# SH08_-_OMAP-L137_EMIF_A.net
KiCad netlist of a schematic drawn in Altium Designer
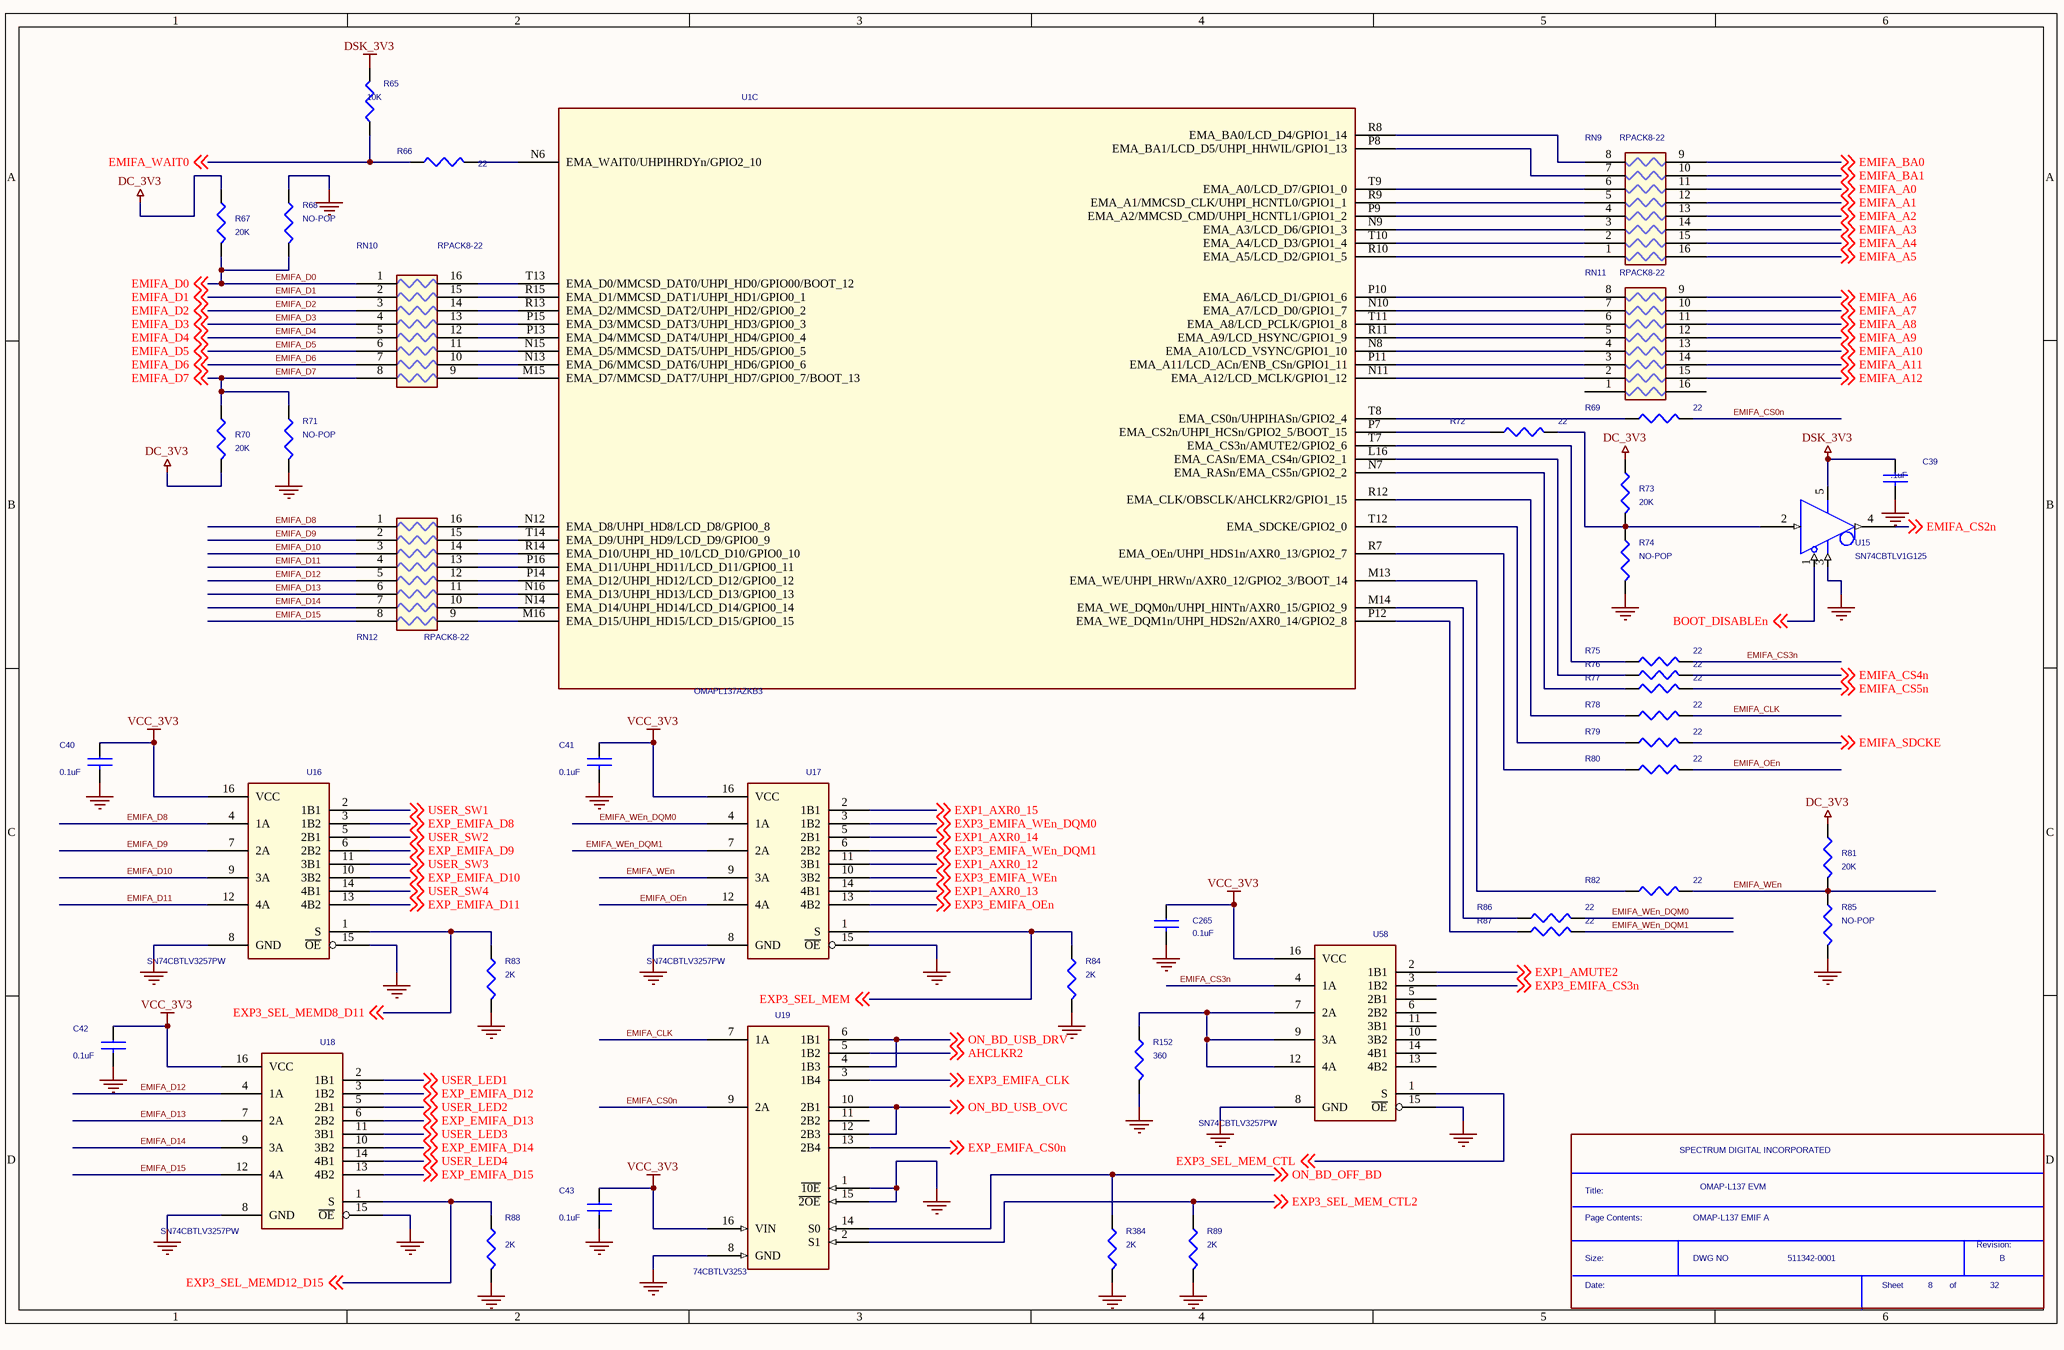
[diagram p0: SH08 - OMAP-L137 EMIF A.SchDoc]

(export (version "E")
  (design (tool "Eeschema 10.0.6"))
  (components
    (comp (ref "C39")
      (value ".1uF")
      (footprint "c402-25")
      (fields (field (name "PART #") "101587-1100R"))
      (libsource (lib "*") (part "CAP NP_2"))
    )
    (comp (ref "C40")
      (value "0.1uF")
      (footprint "c402-25")
      (fields (field (name "PART #") "101587-1100R"))
      (libsource (lib "*") (part "CAP NP"))
    )
    (comp (ref "C41")
      (value "0.1uF")
      (footprint "c402-25")
      (fields (field (name "PART #") "101587-1100R"))
      (libsource (lib "*") (part "CAP NP"))
    )
    (comp (ref "C42")
      (value "0.1uF")
      (footprint "c402-25")
      (fields (field (name "PART #") "101587-1100R"))
      (libsource (lib "*") (part "CAP NP"))
    )
    (comp (ref "C43")
      (value "0.1uF")
      (footprint "c402-25")
      (fields (field (name "PART #") "101587-1100R"))
      (libsource (lib "*") (part "CAP NP"))
    )
    (comp (ref "C265")
      (value "0.1uF")
      (footprint "c402-25")
      (fields (field (name "PART #") "101587-1100R"))
      (libsource (lib "*") (part "CAP NP_2"))
    )
    (comp (ref "R65")
      (value "10K")
      (footprint "r402-25")
      (fields (field (name "PART #") "101370-1003R"))
      (libsource (lib "*") (part "R"))
    )
    (comp (ref "R66")
      (value "22")
      (footprint "r402-25")
      (fields (field (name "PART #") "101370-2200R"))
      (libsource (lib "*") (part "R"))
    )
    (comp (ref "R67")
      (value "20K")
      (footprint "r402-25")
      (fields (field (name "PART #") "101370-2003R"))
      (libsource (lib "*") (part "R_1"))
    )
    (comp (ref "R68")
      (value "NO-POP")
      (footprint "r402-25")
      (fields (field (name "PART #") "R0402-NOPOP"))
      (libsource (lib "*") (part "R_1"))
    )
    (comp (ref "R69")
      (value "22")
      (footprint "r402-25")
      (fields (field (name "PART #") "101370-2200R"))
      (libsource (lib "*") (part "R"))
    )
    (comp (ref "R70")
      (value "20K")
      (footprint "r402-25")
      (fields (field (name "PART #") "101370-2003R"))
      (libsource (lib "*") (part "R_1"))
    )
    (comp (ref "R71")
      (value "NO-POP")
      (footprint "r402-25")
      (fields (field (name "PART #") "R0402-NOPOP"))
      (libsource (lib "*") (part "R_1"))
    )
    (comp (ref "R72")
      (value "22")
      (footprint "r402-25")
      (fields (field (name "PART #") "101370-2200R"))
      (libsource (lib "*") (part "R"))
    )
    (comp (ref "R73")
      (value "20K")
      (footprint "r402-25")
      (fields (field (name "PART #") "101370-2003R"))
      (libsource (lib "*") (part "R_1"))
    )
    (comp (ref "R74")
      (value "NO-POP")
      (footprint "r402-25")
      (fields (field (name "PART #") "R0402-NOPOP"))
      (libsource (lib "*") (part "R_1"))
    )
    (comp (ref "R75")
      (value "22")
      (footprint "r402-25")
      (fields (field (name "PART #") "101370-2200R"))
      (libsource (lib "*") (part "R"))
    )
    (comp (ref "R76")
      (value "22")
      (footprint "r402-25")
      (fields (field (name "PART #") "101370-2200R"))
      (libsource (lib "*") (part "R"))
    )
    (comp (ref "R77")
      (value "22")
      (footprint "r402-25")
      (fields (field (name "PART #") "101370-2200R"))
      (libsource (lib "*") (part "R"))
    )
    (comp (ref "R78")
      (value "22")
      (footprint "r402-25")
      (fields (field (name "PART #") "101370-2200R"))
      (libsource (lib "*") (part "R"))
    )
    (comp (ref "R79")
      (value "22")
      (footprint "r402-25")
      (fields (field (name "PART #") "101370-2200R"))
      (libsource (lib "*") (part "R"))
    )
    (comp (ref "R80")
      (value "22")
      (footprint "r402-25")
      (fields (field (name "PART #") "101370-2200R"))
      (libsource (lib "*") (part "R"))
    )
    (comp (ref "R81")
      (value "20K")
      (footprint "r402-25")
      (fields (field (name "PART #") "101370-2003R"))
      (libsource (lib "*") (part "R_1"))
    )
    (comp (ref "R82")
      (value "22")
      (footprint "r402-25")
      (fields (field (name "PART #") "101370-2200R"))
      (libsource (lib "*") (part "R"))
    )
    (comp (ref "R83")
      (value "2K")
      (footprint "r402-25")
      (fields (field (name "PART #") "101370-2002R"))
      (libsource (lib "*") (part "R"))
    )
    (comp (ref "R84")
      (value "2K")
      (footprint "r402-25")
      (fields (field (name "PART #") "101370-2002R"))
      (libsource (lib "*") (part "R"))
    )
    (comp (ref "R85")
      (value "NO-POP")
      (footprint "r402-25")
      (fields (field (name "PART #") "R0402-NOPOP"))
      (libsource (lib "*") (part "R_1"))
    )
    (comp (ref "R86")
      (value "22")
      (footprint "r402-25")
      (fields (field (name "PART #") "101370-2200R"))
      (libsource (lib "*") (part "R"))
    )
    (comp (ref "R87")
      (value "22")
      (footprint "r402-25")
      (fields (field (name "PART #") "101370-2200R"))
      (libsource (lib "*") (part "R"))
    )
    (comp (ref "R88")
      (value "2K")
      (footprint "r402-25")
      (fields (field (name "PART #") "101370-2002R"))
      (libsource (lib "*") (part "R"))
    )
    (comp (ref "R89")
      (value "2K")
      (footprint "r402-25")
      (fields (field (name "PART #") "101370-2002R"))
      (libsource (lib "*") (part "R"))
    )
    (comp (ref "R152")
      (value "360")
      (footprint "r402-25")
      (fields (field (name "PART #") "101370-3601R"))
      (libsource (lib "*") (part "R"))
    )
    (comp (ref "R384")
      (value "2K")
      (footprint "r402-25")
      (fields (field (name "PART #") "101370-2002R"))
      (libsource (lib "*") (part "R"))
    )
    (comp (ref "RN9")
      (value "RPACK8-22")
      (footprint "rpak16-10x25-2hv")
      (fields (field (name "PART #") "101069-2200R"))
      (libsource (lib "*") (part "RESISTOR DIP 8_0"))
    )
    (comp (ref "RN10")
      (value "RPACK8-22")
      (footprint "rpak16-10x25-2hv")
      (fields (field (name "PART #") "101069-2200R"))
      (libsource (lib "*") (part "RESISTOR DIP 8_0"))
    )
    (comp (ref "RN11")
      (value "RPACK8-22")
      (footprint "rpak16-10x25-2hv")
      (fields (field (name "PART #") "101069-2200R"))
      (libsource (lib "*") (part "RESISTOR DIP 8_0"))
    )
    (comp (ref "RN12")
      (value "RPACK8-22")
      (footprint "rpak16-10x25-2hv")
      (fields (field (name "PART #") "101069-2200R"))
      (libsource (lib "*") (part "RESISTOR DIP 8_0"))
    )
    (comp (ref "U1")
      (value "OMAPL137AZKB3")
      (footprint "skt256-6064")
      (fields (field (name "PART #") "102772-0001"))
      (libsource (lib "*") (part "PRIMUS_BGA_1"))
    )
    (comp (ref "U15")
      (value "SN74CBTLV1G125")
      (footprint "DCK")
      (fields (field (name "PART #") "101689-0125R"))
      (libsource (lib "*") (part "SN74LVC1G125"))
    )
    (comp (ref "U16")
      (value "SN74CBTLV3257PW")
      (footprint "TSSOP-16")
      (description "IC, Quad 2-1 Multiplexer")
      (fields (field (name "MFG") "TI") (field (name "PART #") "101670-0001R"))
      (libsource (lib "*") (part "SN74CBT3257PW"))
    )
    (comp (ref "U17")
      (value "SN74CBTLV3257PW")
      (footprint "TSSOP-16")
      (description "IC, Quad 2-1 Multiplexer")
      (fields (field (name "MFG") "TI") (field (name "PART #") "101670-0001R"))
      (libsource (lib "*") (part "SN74CBT3257PW"))
    )
    (comp (ref "U18")
      (value "SN74CBTLV3257PW")
      (footprint "TSSOP-16")
      (description "IC, Quad 2-1 Multiplexer")
      (fields (field (name "MFG") "TI") (field (name "PART #") "101670-0001R"))
      (libsource (lib "*") (part "SN74CBT3257PW"))
    )
    (comp (ref "U19")
      (value "74CBTLV3253")
      (footprint "tssop16-14x70")
      (fields (field (name "PART #") "101433-0001R"))
      (libsource (lib "*") (part "74CBTLV253_0"))
    )
    (comp (ref "U58")
      (value "SN74CBTLV3257PW")
      (footprint "TSSOP-16")
      (description "IC, Quad 2-1 Multiplexer")
      (fields (field (name "MFG") "TI") (field (name "PART #") "101670-0001R"))
      (libsource (lib "*") (part "SN74CBT3257PW"))
    )
  )
  (nets
    (net (code "1") (name "/EMIFA_CLK") (class "Default")
      (node (ref "R78") (pin "2") (pinfunction "2_2") (pintype "passive"))
      (node (ref "U19") (pin "7") (pinfunction "1A_7") (pintype "passive"))
    )
    (net (code "2") (name "/EMIFA_CS0n") (class "Default")
      (node (ref "R69") (pin "2") (pinfunction "2_2") (pintype "passive"))
      (node (ref "U19") (pin "9") (pinfunction "2A_9") (pintype "passive"))
    )
    (net (code "3") (name "/EMIFA_CS3n") (class "Default")
      (node (ref "R75") (pin "2") (pinfunction "2_2") (pintype "passive"))
      (node (ref "U58") (pin "4") (pinfunction "1A_4") (pintype "passive"))
    )
    (net (code "4") (name "/EMIFA_D8") (class "Default")
      (node (ref "RN12") (pin "1") (pinfunction "1_1") (pintype "passive"))
      (node (ref "U16") (pin "4") (pinfunction "1A_4") (pintype "passive"))
    )
    (net (code "5") (name "/EMIFA_D9") (class "Default")
      (node (ref "RN12") (pin "2") (pinfunction "2_2") (pintype "passive"))
      (node (ref "U16") (pin "7") (pinfunction "2A_7") (pintype "passive"))
    )
    (net (code "6") (name "/EMIFA_D10") (class "Default")
      (node (ref "RN12") (pin "3") (pinfunction "3_3") (pintype "passive"))
      (node (ref "U16") (pin "9") (pinfunction "3A_9") (pintype "passive"))
    )
    (net (code "7") (name "/EMIFA_D11") (class "Default")
      (node (ref "RN12") (pin "4") (pinfunction "4_4") (pintype "passive"))
      (node (ref "U16") (pin "12") (pinfunction "4A_12") (pintype "passive"))
    )
    (net (code "8") (name "/EMIFA_D12") (class "Default")
      (node (ref "RN12") (pin "5") (pinfunction "5_5") (pintype "passive"))
      (node (ref "U18") (pin "4") (pinfunction "1A_4") (pintype "passive"))
    )
    (net (code "9") (name "/EMIFA_D13") (class "Default")
      (node (ref "RN12") (pin "6") (pinfunction "6_6") (pintype "passive"))
      (node (ref "U18") (pin "7") (pinfunction "2A_7") (pintype "passive"))
    )
    (net (code "10") (name "/EMIFA_D14") (class "Default")
      (node (ref "RN12") (pin "7") (pinfunction "7_7") (pintype "passive"))
      (node (ref "U18") (pin "9") (pinfunction "3A_9") (pintype "passive"))
    )
    (net (code "11") (name "/EMIFA_D15") (class "Default")
      (node (ref "RN12") (pin "8") (pinfunction "8_8") (pintype "passive"))
      (node (ref "U18") (pin "12") (pinfunction "4A_12") (pintype "passive"))
    )
    (net (code "12") (name "/EMIFA_OEn") (class "Default")
      (node (ref "R80") (pin "2") (pinfunction "2_2") (pintype "passive"))
      (node (ref "U17") (pin "12") (pinfunction "4A_12") (pintype "passive"))
    )
    (net (code "13") (name "/EMIFA_WEn") (class "Default")
      (node (ref "R81") (pin "2") (pinfunction "2_2") (pintype "passive"))
      (node (ref "R82") (pin "2") (pinfunction "2_2") (pintype "passive"))
      (node (ref "R85") (pin "1") (pinfunction "1_1") (pintype "passive"))
      (node (ref "U17") (pin "9") (pinfunction "3A_9") (pintype "passive"))
    )
    (net (code "14") (name "/EMIFA_WEn_DQM0") (class "Default")
      (node (ref "R86") (pin "2") (pinfunction "2_2") (pintype "passive"))
      (node (ref "U17") (pin "4") (pinfunction "1A_4") (pintype "passive"))
    )
    (net (code "15") (name "/EMIFA_WEn_DQM1") (class "Default")
      (node (ref "R87") (pin "2") (pinfunction "2_2") (pintype "passive"))
      (node (ref "U17") (pin "7") (pinfunction "2A_7") (pintype "passive"))
    )
    (net (code "16") (name "AHCLKR2") (class "Default")
      (node (ref "U19") (pin "5") (pinfunction "1B2_5") (pintype "passive"))
    )
    (net (code "17") (name "BOOT_DISABLEn") (class "Default")
      (node (ref "U15") (pin "1") (pinfunction "OE_1") (pintype "input"))
    )
    (net (code "18") (name "DC_3V3") (class "Default")
      (node (ref "R67") (pin "1") (pinfunction "1_1") (pintype "passive"))
      (node (ref "R70") (pin "2") (pinfunction "2_2") (pintype "passive"))
      (node (ref "R73") (pin "1") (pinfunction "1_1") (pintype "passive"))
      (node (ref "R81") (pin "1") (pinfunction "1_1") (pintype "passive"))
    )
    (net (code "19") (name "DSK_3V3") (class "Default")
      (node (ref "C39") (pin "1") (pinfunction "1_1") (pintype "passive"))
      (node (ref "R65") (pin "1") (pinfunction "1_1") (pintype "passive"))
      (node (ref "U15") (pin "5") (pinfunction "VCC_5") (pintype "passive"))
    )
    (net (code "20") (name "EMIFA_A0") (class "Default")
      (node (ref "RN9") (pin "11") (pinfunction "11_11") (pintype "passive"))
    )
    (net (code "21") (name "EMIFA_A1") (class "Default")
      (node (ref "RN9") (pin "12") (pinfunction "12_12") (pintype "passive"))
    )
    (net (code "22") (name "EMIFA_A2") (class "Default")
      (node (ref "RN9") (pin "13") (pinfunction "13_13") (pintype "passive"))
    )
    (net (code "23") (name "EMIFA_A3") (class "Default")
      (node (ref "RN9") (pin "14") (pinfunction "14_14") (pintype "passive"))
    )
    (net (code "24") (name "EMIFA_A4") (class "Default")
      (node (ref "RN9") (pin "15") (pinfunction "15_15") (pintype "passive"))
    )
    (net (code "25") (name "EMIFA_A5") (class "Default")
      (node (ref "RN9") (pin "16") (pinfunction "16_16") (pintype "passive"))
    )
    (net (code "26") (name "EMIFA_A6") (class "Default")
      (node (ref "RN11") (pin "9") (pinfunction "9_9") (pintype "passive"))
    )
    (net (code "27") (name "EMIFA_A7") (class "Default")
      (node (ref "RN11") (pin "10") (pinfunction "10_10") (pintype "passive"))
    )
    (net (code "28") (name "EMIFA_A8") (class "Default")
      (node (ref "RN11") (pin "11") (pinfunction "11_11") (pintype "passive"))
    )
    (net (code "29") (name "EMIFA_A9") (class "Default")
      (node (ref "RN11") (pin "12") (pinfunction "12_12") (pintype "passive"))
    )
    (net (code "30") (name "EMIFA_A10") (class "Default")
      (node (ref "RN11") (pin "13") (pinfunction "13_13") (pintype "passive"))
    )
    (net (code "31") (name "EMIFA_A11") (class "Default")
      (node (ref "RN11") (pin "14") (pinfunction "14_14") (pintype "passive"))
    )
    (net (code "32") (name "EMIFA_A12") (class "Default")
      (node (ref "RN11") (pin "15") (pinfunction "15_15") (pintype "passive"))
    )
    (net (code "33") (name "EMIFA_BA0") (class "Default")
      (node (ref "RN9") (pin "9") (pinfunction "9_9") (pintype "passive"))
    )
    (net (code "34") (name "EMIFA_BA1") (class "Default")
      (node (ref "RN9") (pin "10") (pinfunction "10_10") (pintype "passive"))
    )
    (net (code "35") (name "EMIFA_CS2n") (class "Default")
      (node (ref "U15") (pin "4") (pinfunction "O_4") (pintype "output"))
    )
    (net (code "36") (name "EMIFA_CS4n") (class "Default")
      (node (ref "R76") (pin "2") (pinfunction "2_2") (pintype "passive"))
    )
    (net (code "37") (name "EMIFA_CS5n") (class "Default")
      (node (ref "R77") (pin "2") (pinfunction "2_2") (pintype "passive"))
    )
    (net (code "38") (name "EMIFA_D0") (class "Default")
      (node (ref "R67") (pin "2") (pinfunction "2_2") (pintype "passive"))
      (node (ref "R68") (pin "2") (pinfunction "2_2") (pintype "passive"))
      (node (ref "RN10") (pin "1") (pinfunction "1_1") (pintype "passive"))
    )
    (net (code "39") (name "EMIFA_D1") (class "Default")
      (node (ref "RN10") (pin "2") (pinfunction "2_2") (pintype "passive"))
    )
    (net (code "40") (name "EMIFA_D2") (class "Default")
      (node (ref "RN10") (pin "3") (pinfunction "3_3") (pintype "passive"))
    )
    (net (code "41") (name "EMIFA_D3") (class "Default")
      (node (ref "RN10") (pin "4") (pinfunction "4_4") (pintype "passive"))
    )
    (net (code "42") (name "EMIFA_D4") (class "Default")
      (node (ref "RN10") (pin "5") (pinfunction "5_5") (pintype "passive"))
    )
    (net (code "43") (name "EMIFA_D5") (class "Default")
      (node (ref "RN10") (pin "6") (pinfunction "6_6") (pintype "passive"))
    )
    (net (code "44") (name "EMIFA_D6") (class "Default")
      (node (ref "RN10") (pin "7") (pinfunction "7_7") (pintype "passive"))
    )
    (net (code "45") (name "EMIFA_D7") (class "Default")
      (node (ref "R70") (pin "1") (pinfunction "1_1") (pintype "passive"))
      (node (ref "R71") (pin "1") (pinfunction "1_1") (pintype "passive"))
      (node (ref "RN10") (pin "8") (pinfunction "8_8") (pintype "passive"))
    )
    (net (code "46") (name "EMIFA_SDCKE") (class "Default")
      (node (ref "R79") (pin "2") (pinfunction "2_2") (pintype "passive"))
    )
    (net (code "47") (name "EMIFA_WAIT0") (class "Default")
      (node (ref "R65") (pin "2") (pinfunction "2_2") (pintype "passive"))
      (node (ref "R66") (pin "2") (pinfunction "2_2") (pintype "passive"))
    )
    (net (code "48") (name "EXP1_AMUTE2") (class "Default")
      (node (ref "U58") (pin "2") (pinfunction "1B1_2") (pintype "passive"))
    )
    (net (code "49") (name "EXP1_AXR0_12") (class "Default")
      (node (ref "U17") (pin "11") (pinfunction "3B1_11") (pintype "passive"))
    )
    (net (code "50") (name "EXP1_AXR0_13") (class "Default")
      (node (ref "U17") (pin "14") (pinfunction "4B1_14") (pintype "passive"))
    )
    (net (code "51") (name "EXP1_AXR0_14") (class "Default")
      (node (ref "U17") (pin "5") (pinfunction "2B1_5") (pintype "passive"))
    )
    (net (code "52") (name "EXP1_AXR0_15") (class "Default")
      (node (ref "U17") (pin "2") (pinfunction "1B1_2") (pintype "passive"))
    )
    (net (code "53") (name "EXP3_EMIFA_CLK") (class "Default")
      (node (ref "U19") (pin "3") (pinfunction "1B4_3") (pintype "passive"))
    )
    (net (code "54") (name "EXP3_EMIFA_CS3n") (class "Default")
      (node (ref "U58") (pin "3") (pinfunction "1B2_3") (pintype "passive"))
    )
    (net (code "55") (name "EXP3_EMIFA_OEn") (class "Default")
      (node (ref "U17") (pin "13") (pinfunction "4B2_13") (pintype "passive"))
    )
    (net (code "56") (name "EXP3_EMIFA_WEn") (class "Default")
      (node (ref "U17") (pin "10") (pinfunction "3B2_10") (pintype "passive"))
    )
    (net (code "57") (name "EXP3_EMIFA_WEn_DQM0") (class "Default")
      (node (ref "U17") (pin "3") (pinfunction "1B2_3") (pintype "passive"))
    )
    (net (code "58") (name "EXP3_EMIFA_WEn_DQM1") (class "Default")
      (node (ref "U17") (pin "6") (pinfunction "2B2_6") (pintype "passive"))
    )
    (net (code "59") (name "EXP3_SEL_MEM") (class "Default")
      (node (ref "R84") (pin "1") (pinfunction "1_1") (pintype "passive"))
      (node (ref "U17") (pin "1") (pinfunction "S_1") (pintype "passive"))
    )
    (net (code "60") (name "EXP3_SEL_MEMD8_D11") (class "Default")
      (node (ref "R83") (pin "1") (pinfunction "1_1") (pintype "passive"))
      (node (ref "U16") (pin "1") (pinfunction "S_1") (pintype "passive"))
    )
    (net (code "61") (name "EXP3_SEL_MEMD12_D15") (class "Default")
      (node (ref "R88") (pin "1") (pinfunction "1_1") (pintype "passive"))
      (node (ref "U18") (pin "1") (pinfunction "S_1") (pintype "passive"))
    )
    (net (code "62") (name "EXP3_SEL_MEM_CTL") (class "Default")
      (node (ref "U58") (pin "1") (pinfunction "S_1") (pintype "passive"))
    )
    (net (code "63") (name "EXP3_SEL_MEM_CTL2") (class "Default")
      (node (ref "R89") (pin "1") (pinfunction "1_1") (pintype "passive"))
      (node (ref "U19") (pin "2") (pinfunction "S1_2") (pintype "input"))
    )
    (net (code "64") (name "EXP_EMIFA_CS0n") (class "Default")
      (node (ref "U19") (pin "13") (pinfunction "2B4_13") (pintype "passive"))
    )
    (net (code "65") (name "EXP_EMIFA_D8") (class "Default")
      (node (ref "U16") (pin "3") (pinfunction "1B2_3") (pintype "passive"))
    )
    (net (code "66") (name "EXP_EMIFA_D9") (class "Default")
      (node (ref "U16") (pin "6") (pinfunction "2B2_6") (pintype "passive"))
    )
    (net (code "67") (name "EXP_EMIFA_D10") (class "Default")
      (node (ref "U16") (pin "10") (pinfunction "3B2_10") (pintype "passive"))
    )
    (net (code "68") (name "EXP_EMIFA_D11") (class "Default")
      (node (ref "U16") (pin "13") (pinfunction "4B2_13") (pintype "passive"))
    )
    (net (code "69") (name "EXP_EMIFA_D12") (class "Default")
      (node (ref "U18") (pin "3") (pinfunction "1B2_3") (pintype "passive"))
    )
    (net (code "70") (name "EXP_EMIFA_D13") (class "Default")
      (node (ref "U18") (pin "6") (pinfunction "2B2_6") (pintype "passive"))
    )
    (net (code "71") (name "EXP_EMIFA_D14") (class "Default")
      (node (ref "U18") (pin "10") (pinfunction "3B2_10") (pintype "passive"))
    )
    (net (code "72") (name "EXP_EMIFA_D15") (class "Default")
      (node (ref "U18") (pin "13") (pinfunction "4B2_13") (pintype "passive"))
    )
    (net (code "73") (name "GND") (class "Default")
      (node (ref "C265") (pin "2") (pinfunction "2_2") (pintype "passive"))
      (node (ref "C39") (pin "2") (pinfunction "2_2") (pintype "passive"))
      (node (ref "C40") (pin "2") (pinfunction "2_2") (pintype "passive"))
      (node (ref "C41") (pin "2") (pinfunction "2_2") (pintype "passive"))
      (node (ref "C42") (pin "2") (pinfunction "2_2") (pintype "passive"))
      (node (ref "C43") (pin "2") (pinfunction "2_2") (pintype "passive"))
      (node (ref "R152") (pin "2") (pinfunction "2_2") (pintype "passive"))
      (node (ref "R384") (pin "2") (pinfunction "2_2") (pintype "passive"))
      (node (ref "R68") (pin "1") (pinfunction "1_1") (pintype "passive"))
      (node (ref "R71") (pin "2") (pinfunction "2_2") (pintype "passive"))
      (node (ref "R74") (pin "2") (pinfunction "2_2") (pintype "passive"))
      (node (ref "R83") (pin "2") (pinfunction "2_2") (pintype "passive"))
      (node (ref "R84") (pin "2") (pinfunction "2_2") (pintype "passive"))
      (node (ref "R85") (pin "2") (pinfunction "2_2") (pintype "passive"))
      (node (ref "R88") (pin "2") (pinfunction "2_2") (pintype "passive"))
      (node (ref "R89") (pin "2") (pinfunction "2_2") (pintype "passive"))
      (node (ref "U15") (pin "3") (pinfunction "GND_3") (pintype "input"))
      (node (ref "U16") (pin "15") (pinfunction "~{OE}_15") (pintype "passive"))
      (node (ref "U16") (pin "8") (pinfunction "GND_8") (pintype "passive"))
      (node (ref "U17") (pin "15") (pinfunction "~{OE}_15") (pintype "passive"))
      (node (ref "U17") (pin "8") (pinfunction "GND_8") (pintype "passive"))
      (node (ref "U18") (pin "15") (pinfunction "~{OE}_15") (pintype "passive"))
      (node (ref "U18") (pin "8") (pinfunction "GND_8") (pintype "passive"))
      (node (ref "U19") (pin "1") (pinfunction "~{10E}_1") (pintype "input"))
      (node (ref "U19") (pin "15") (pinfunction "~{2OE}_15") (pintype "input"))
      (node (ref "U19") (pin "8") (pinfunction "GND_8") (pintype "input"))
      (node (ref "U58") (pin "15") (pinfunction "~{OE}_15") (pintype "passive"))
      (node (ref "U58") (pin "8") (pinfunction "GND_8") (pintype "passive"))
    )
    (net (code "74") (name "Net-(U1C-EMA_A0{slash}LCD_D7{slash}GPIO1_0)") (class "Default")
      (node (ref "RN9") (pin "6") (pinfunction "6_6") (pintype "passive"))
      (node (ref "U1") (pin "T9") (pinfunction "EMA_A0/LCD_D7/GPIO1_0_T9") (pintype "passive"))
    )
    (net (code "75") (name "Net-(U1C-EMA_A1{slash}MMCSD_CLK{slash}UHPI_HCNTL0{slash}GPIO1_1)") (class "Default")
      (node (ref "RN9") (pin "5") (pinfunction "5_5") (pintype "passive"))
      (node (ref "U1") (pin "R9") (pinfunction "EMA_A1/MMCSD_CLK/UHPI_HCNTL0/GPIO1_1_R9") (pintype "passive"))
    )
    (net (code "76") (name "Net-(U1C-EMA_A2{slash}MMCSD_CMD{slash}UHPI_HCNTL1{slash}GPIO1_2)") (class "Default")
      (node (ref "RN9") (pin "4") (pinfunction "4_4") (pintype "passive"))
      (node (ref "U1") (pin "P9") (pinfunction "EMA_A2/MMCSD_CMD/UHPI_HCNTL1/GPIO1_2_P9") (pintype "passive"))
    )
    (net (code "77") (name "Net-(U1C-EMA_A3{slash}LCD_D6{slash}GPIO1_3)") (class "Default")
      (node (ref "RN9") (pin "3") (pinfunction "3_3") (pintype "passive"))
      (node (ref "U1") (pin "N9") (pinfunction "EMA_A3/LCD_D6/GPIO1_3_N9") (pintype "passive"))
    )
    (net (code "78") (name "Net-(U1C-EMA_A4{slash}LCD_D3{slash}GPIO1_4)") (class "Default")
      (node (ref "RN9") (pin "2") (pinfunction "2_2") (pintype "passive"))
      (node (ref "U1") (pin "T10") (pinfunction "EMA_A4/LCD_D3/GPIO1_4_T10") (pintype "passive"))
    )
    (net (code "79") (name "Net-(U1C-EMA_A5{slash}LCD_D2{slash}GPIO1_5)") (class "Default")
      (node (ref "RN9") (pin "1") (pinfunction "1_1") (pintype "passive"))
      (node (ref "U1") (pin "R10") (pinfunction "EMA_A5/LCD_D2/GPIO1_5_R10") (pintype "passive"))
    )
    (net (code "80") (name "Net-(U1C-EMA_A6{slash}LCD_D1{slash}GPIO1_6)") (class "Default")
      (node (ref "RN11") (pin "8") (pinfunction "8_8") (pintype "passive"))
      (node (ref "U1") (pin "P10") (pinfunction "EMA_A6/LCD_D1/GPIO1_6_P10") (pintype "passive"))
    )
    (net (code "81") (name "Net-(U1C-EMA_A7{slash}LCD_D0{slash}GPIO1_7)") (class "Default")
      (node (ref "RN11") (pin "7") (pinfunction "7_7") (pintype "passive"))
      (node (ref "U1") (pin "N10") (pinfunction "EMA_A7/LCD_D0/GPIO1_7_N10") (pintype "passive"))
    )
    (net (code "82") (name "Net-(U1C-EMA_A8{slash}LCD_PCLK{slash}GPIO1_8)") (class "Default")
      (node (ref "RN11") (pin "6") (pinfunction "6_6") (pintype "passive"))
      (node (ref "U1") (pin "T11") (pinfunction "EMA_A8/LCD_PCLK/GPIO1_8_T11") (pintype "passive"))
    )
    (net (code "83") (name "Net-(U1C-EMA_A9{slash}LCD_HSYNC{slash}GPIO1_9)") (class "Default")
      (node (ref "RN11") (pin "5") (pinfunction "5_5") (pintype "passive"))
      (node (ref "U1") (pin "R11") (pinfunction "EMA_A9/LCD_HSYNC/GPIO1_9_R11") (pintype "passive"))
    )
    (net (code "84") (name "Net-(U1C-EMA_A10{slash}LCD_VSYNC{slash}GPIO1_10)") (class "Default")
      (node (ref "RN11") (pin "4") (pinfunction "4_4") (pintype "passive"))
      (node (ref "U1") (pin "N8") (pinfunction "EMA_A10/LCD_VSYNC/GPIO1_10_N8") (pintype "passive"))
    )
    (net (code "85") (name "Net-(U1C-EMA_A11{slash}LCD_ACn{slash}ENB_CSn{slash}GPIO1_11)") (class "Default")
      (node (ref "RN11") (pin "3") (pinfunction "3_3") (pintype "passive"))
      (node (ref "U1") (pin "P11") (pinfunction "EMA_A11/LCD_ACn/ENB_CSn/GPIO1_11_P11") (pintype "passive"))
    )
    (net (code "86") (name "Net-(U1C-EMA_A12{slash}LCD_MCLK{slash}GPIO1_12)") (class "Default")
      (node (ref "RN11") (pin "2") (pinfunction "2_2") (pintype "passive"))
      (node (ref "U1") (pin "N11") (pinfunction "EMA_A12/LCD_MCLK/GPIO1_12_N11") (pintype "passive"))
    )
    (net (code "87") (name "Net-(U1C-EMA_BA0{slash}LCD_D4{slash}GPIO1_14)") (class "Default")
      (node (ref "RN9") (pin "8") (pinfunction "8_8") (pintype "passive"))
      (node (ref "U1") (pin "R8") (pinfunction "EMA_BA0/LCD_D4/GPIO1_14_R8") (pintype "passive"))
    )
    (net (code "88") (name "Net-(U1C-EMA_BA1{slash}LCD_D5{slash}UHPI_HHWIL{slash}GPIO1_13)") (class "Default")
      (node (ref "RN9") (pin "7") (pinfunction "7_7") (pintype "passive"))
      (node (ref "U1") (pin "P8") (pinfunction "EMA_BA1/LCD_D5/UHPI_HHWIL/GPIO1_13_P8") (pintype "passive"))
    )
    (net (code "89") (name "Net-(U1C-EMA_CASn{slash}EMA_CS4n{slash}GPIO2_1)") (class "Default")
      (node (ref "R76") (pin "1") (pinfunction "1_1") (pintype "passive"))
      (node (ref "U1") (pin "L16") (pinfunction "EMA_CASn/EMA_CS4n/GPIO2_1_L16") (pintype "passive"))
    )
    (net (code "90") (name "Net-(U1C-EMA_CLK{slash}OBSCLK{slash}AHCLKR2{slash}GPIO1_15)") (class "Default")
      (node (ref "R78") (pin "1") (pinfunction "1_1") (pintype "passive"))
      (node (ref "U1") (pin "R12") (pinfunction "EMA_CLK/OBSCLK/AHCLKR2/GPIO1_15_R12") (pintype "passive"))
    )
    (net (code "91") (name "Net-(U1C-EMA_CS0n{slash}UHPIHASn{slash}GPIO2_4)") (class "Default")
      (node (ref "R69") (pin "1") (pinfunction "1_1") (pintype "passive"))
      (node (ref "U1") (pin "T8") (pinfunction "EMA_CS0n/UHPIHASn/GPIO2_4_T8") (pintype "passive"))
    )
    (net (code "92") (name "Net-(U1C-EMA_CS2n{slash}UHPI_HCSn{slash}GPIO2_5{slash}BOOT_15)") (class "Default")
      (node (ref "R72") (pin "1") (pinfunction "1_1") (pintype "passive"))
      (node (ref "U1") (pin "P7") (pinfunction "EMA_CS2n/UHPI_HCSn/GPIO2_5/BOOT_15_P7") (pintype "passive"))
    )
    (net (code "93") (name "Net-(U1C-EMA_CS3n{slash}AMUTE2{slash}GPIO2_6)") (class "Default")
      (node (ref "R75") (pin "1") (pinfunction "1_1") (pintype "passive"))
      (node (ref "U1") (pin "T7") (pinfunction "EMA_CS3n/AMUTE2/GPIO2_6_T7") (pintype "passive"))
    )
    (net (code "94") (name "Net-(U1C-EMA_D0{slash}MMCSD_DAT0{slash}UHPI_HD0{slash}GPIO00{slash}BOOT_12)") (class "Default")
      (node (ref "RN10") (pin "16") (pinfunction "16_16") (pintype "passive"))
      (node (ref "U1") (pin "T13") (pinfunction "EMA_D0/MMCSD_DAT0/UHPI_HD0/GPIO00/BOOT_12_T13") (pintype "passive"))
    )
    (net (code "95") (name "Net-(U1C-EMA_D1{slash}MMCSD_DAT1{slash}UHPI_HD1{slash}GPIO0_1)") (class "Default")
      (node (ref "RN10") (pin "15") (pinfunction "15_15") (pintype "passive"))
      (node (ref "U1") (pin "R15") (pinfunction "EMA_D1/MMCSD_DAT1/UHPI_HD1/GPIO0_1_R15") (pintype "passive"))
    )
    (net (code "96") (name "Net-(U1C-EMA_D2{slash}MMCSD_DAT2{slash}UHPI_HD2{slash}GPIO0_2)") (class "Default")
      (node (ref "RN10") (pin "14") (pinfunction "14_14") (pintype "passive"))
      (node (ref "U1") (pin "R13") (pinfunction "EMA_D2/MMCSD_DAT2/UHPI_HD2/GPIO0_2_R13") (pintype "passive"))
    )
    (net (code "97") (name "Net-(U1C-EMA_D3{slash}MMCSD_DAT3{slash}UHPI_HD3{slash}GPIO0_3)") (class "Default")
      (node (ref "RN10") (pin "13") (pinfunction "13_13") (pintype "passive"))
      (node (ref "U1") (pin "P15") (pinfunction "EMA_D3/MMCSD_DAT3/UHPI_HD3/GPIO0_3_P15") (pintype "passive"))
    )
    (net (code "98") (name "Net-(U1C-EMA_D4{slash}MMCSD_DAT4{slash}UHPI_HD4{slash}GPIO0_4)") (class "Default")
      (node (ref "RN10") (pin "12") (pinfunction "12_12") (pintype "passive"))
      (node (ref "U1") (pin "P13") (pinfunction "EMA_D4/MMCSD_DAT4/UHPI_HD4/GPIO0_4_P13") (pintype "passive"))
    )
    (net (code "99") (name "Net-(U1C-EMA_D5{slash}MMCSD_DAT5{slash}UHPI_HD5{slash}GPIO0_5)") (class "Default")
      (node (ref "RN10") (pin "11") (pinfunction "11_11") (pintype "passive"))
      (node (ref "U1") (pin "N15") (pinfunction "EMA_D5/MMCSD_DAT5/UHPI_HD5/GPIO0_5_N15") (pintype "passive"))
    )
    (net (code "100") (name "Net-(U1C-EMA_D6{slash}MMCSD_DAT6{slash}UHPI_HD6{slash}GPIO0_6)") (class "Default")
      (node (ref "RN10") (pin "10") (pinfunction "10_10") (pintype "passive"))
      (node (ref "U1") (pin "N13") (pinfunction "EMA_D6/MMCSD_DAT6/UHPI_HD6/GPIO0_6_N13") (pintype "passive"))
    )
    (net (code "101") (name "Net-(U1C-EMA_D7{slash}MMCSD_DAT7{slash}UHPI_HD7{slash}GPIO0_7{slash}BOOT_13)") (class "Default")
      (node (ref "RN10") (pin "9") (pinfunction "9_9") (pintype "passive"))
      (node (ref "U1") (pin "M15") (pinfunction "EMA_D7/MMCSD_DAT7/UHPI_HD7/GPIO0_7/BOOT_13_M15") (pintype "passive"))
    )
    (net (code "102") (name "Net-(U1C-EMA_D8{slash}UHPI_HD8{slash}LCD_D8{slash}GPIO0_8)") (class "Default")
      (node (ref "RN12") (pin "16") (pinfunction "16_16") (pintype "passive"))
      (node (ref "U1") (pin "N12") (pinfunction "EMA_D8/UHPI_HD8/LCD_D8/GPIO0_8_N12") (pintype "passive"))
    )
    (net (code "103") (name "Net-(U1C-EMA_D9{slash}UHPI_HD9{slash}LCD_D9{slash}GPIO0_9)") (class "Default")
      (node (ref "RN12") (pin "15") (pinfunction "15_15") (pintype "passive"))
      (node (ref "U1") (pin "T14") (pinfunction "EMA_D9/UHPI_HD9/LCD_D9/GPIO0_9_T14") (pintype "passive"))
    )
    (net (code "104") (name "Net-(U1C-EMA_D10{slash}UHPI_HD_10{slash}LCD_D10{slash}GPIO0_10)") (class "Default")
      (node (ref "RN12") (pin "14") (pinfunction "14_14") (pintype "passive"))
      (node (ref "U1") (pin "R14") (pinfunction "EMA_D10/UHPI_HD_10/LCD_D10/GPIO0_10_R14") (pintype "passive"))
    )
    (net (code "105") (name "Net-(U1C-EMA_D11{slash}UHPI_HD11{slash}LCD_D11{slash}GPIO0_11)") (class "Default")
      (node (ref "RN12") (pin "13") (pinfunction "13_13") (pintype "passive"))
      (node (ref "U1") (pin "P16") (pinfunction "EMA_D11/UHPI_HD11/LCD_D11/GPIO0_11_P16") (pintype "passive"))
    )
    (net (code "106") (name "Net-(U1C-EMA_D12{slash}UHPI_HD12{slash}LCD_D12{slash}GPIO0_12)") (class "Default")
      (node (ref "RN12") (pin "12") (pinfunction "12_12") (pintype "passive"))
      (node (ref "U1") (pin "P14") (pinfunction "EMA_D12/UHPI_HD12/LCD_D12/GPIO0_12_P14") (pintype "passive"))
    )
    (net (code "107") (name "Net-(U1C-EMA_D13{slash}UHPI_HD13{slash}LCD_D13{slash}GPIO0_13)") (class "Default")
      (node (ref "RN12") (pin "11") (pinfunction "11_11") (pintype "passive"))
      (node (ref "U1") (pin "N16") (pinfunction "EMA_D13/UHPI_HD13/LCD_D13/GPIO0_13_N16") (pintype "passive"))
    )
    (net (code "108") (name "Net-(U1C-EMA_D14{slash}UHPI_HD14{slash}LCD_D14{slash}GPIO0_14)") (class "Default")
      (node (ref "RN12") (pin "10") (pinfunction "10_10") (pintype "passive"))
      (node (ref "U1") (pin "N14") (pinfunction "EMA_D14/UHPI_HD14/LCD_D14/GPIO0_14_N14") (pintype "passive"))
    )
    (net (code "109") (name "Net-(U1C-EMA_D15{slash}UHPI_HD15{slash}LCD_D15{slash}GPIO0_15)") (class "Default")
      (node (ref "RN12") (pin "9") (pinfunction "9_9") (pintype "passive"))
      (node (ref "U1") (pin "M16") (pinfunction "EMA_D15/UHPI_HD15/LCD_D15/GPIO0_15_M16") (pintype "passive"))
    )
    (net (code "110") (name "Net-(U1C-EMA_OEn{slash}UHPI_HDS1n{slash}AXR0_13{slash}GPIO2_7)") (class "Default")
      (node (ref "R80") (pin "1") (pinfunction "1_1") (pintype "passive"))
      (node (ref "U1") (pin "R7") (pinfunction "EMA_OEn/UHPI_HDS1n/AXR0_13/GPIO2_7_R7") (pintype "passive"))
    )
    (net (code "111") (name "Net-(U1C-EMA_RASn{slash}EMA_CS5n{slash}GPIO2_2)") (class "Default")
      (node (ref "R77") (pin "1") (pinfunction "1_1") (pintype "passive"))
      (node (ref "U1") (pin "N7") (pinfunction "EMA_RASn/EMA_CS5n/GPIO2_2_N7") (pintype "passive"))
    )
    (net (code "112") (name "Net-(U1C-EMA_SDCKE{slash}GPIO2_0)") (class "Default")
      (node (ref "R79") (pin "1") (pinfunction "1_1") (pintype "passive"))
      (node (ref "U1") (pin "T12") (pinfunction "EMA_SDCKE/GPIO2_0_T12") (pintype "passive"))
    )
    (net (code "113") (name "Net-(U1C-EMA_WAIT0{slash}UHPIHRDYn{slash}GPIO2_10)") (class "Default")
      (node (ref "R66") (pin "1") (pinfunction "1_1") (pintype "passive"))
      (node (ref "U1") (pin "N6") (pinfunction "EMA_WAIT0/UHPIHRDYn/GPIO2_10_N6") (pintype "passive"))
    )
    (net (code "114") (name "Net-(U1C-EMA_WE_DQM0n{slash}UHPI_HINTn{slash}AXR0_15{slash}GPIO2_9)") (class "Default")
      (node (ref "R86") (pin "1") (pinfunction "1_1") (pintype "passive"))
      (node (ref "U1") (pin "M14") (pinfunction "EMA_WE_DQM0n/UHPI_HINTn/AXR0_15/GPIO2_9_M14") (pintype "passive"))
    )
    (net (code "115") (name "Net-(U1C-EMA_WE_DQM1n{slash}UHPI_HDS2n{slash}AXR0_14{slash}GPIO2_8)") (class "Default")
      (node (ref "R87") (pin "1") (pinfunction "1_1") (pintype "passive"))
      (node (ref "U1") (pin "P12") (pinfunction "EMA_WE_DQM1n/UHPI_HDS2n/AXR0_14/GPIO2_8_P12") (pintype "passive"))
    )
    (net (code "116") (name "Net-(U1C-EMA_WE{slash}UHPI_HRWn{slash}AXR0_12{slash}GPIO2_3{slash}BOOT_14)") (class "Default")
      (node (ref "R82") (pin "1") (pinfunction "1_1") (pintype "passive"))
      (node (ref "U1") (pin "M13") (pinfunction "EMA_WE/UHPI_HRWn/AXR0_12/GPIO2_3/BOOT_14_M13") (pintype "passive"))
    )
    (net (code "117") (name "Net-(U15-I)") (class "Default")
      (node (ref "R72") (pin "2") (pinfunction "2_2") (pintype "passive"))
      (node (ref "R73") (pin "2") (pinfunction "2_2") (pintype "passive"))
      (node (ref "R74") (pin "1") (pinfunction "1_1") (pintype "passive"))
      (node (ref "U15") (pin "2") (pinfunction "I_2") (pintype "input"))
    )
    (net (code "118") (name "Net-(U58-2A)") (class "Default")
      (node (ref "R152") (pin "1") (pinfunction "1_1") (pintype "passive"))
      (node (ref "U58") (pin "12") (pinfunction "4A_12") (pintype "passive"))
      (node (ref "U58") (pin "7") (pinfunction "2A_7") (pintype "passive"))
      (node (ref "U58") (pin "9") (pinfunction "3A_9") (pintype "passive"))
    )
    (net (code "119") (name "ON_BD_OFF_BD") (class "Default")
      (node (ref "R384") (pin "1") (pinfunction "1_1") (pintype "passive"))
      (node (ref "U19") (pin "14") (pinfunction "S0_14") (pintype "input"))
    )
    (net (code "120") (name "ON_BD_USB_DRV") (class "Default")
      (node (ref "U19") (pin "4") (pinfunction "1B3_4") (pintype "passive"))
      (node (ref "U19") (pin "6") (pinfunction "1B1_6") (pintype "passive"))
    )
    (net (code "121") (name "ON_BD_USB_OVC") (class "Default")
      (node (ref "U19") (pin "10") (pinfunction "2B1_10") (pintype "passive"))
      (node (ref "U19") (pin "12") (pinfunction "2B3_12") (pintype "passive"))
    )
    (net (code "122") (name "USER_LED1") (class "Default")
      (node (ref "U18") (pin "2") (pinfunction "1B1_2") (pintype "passive"))
    )
    (net (code "123") (name "USER_LED2") (class "Default")
      (node (ref "U18") (pin "5") (pinfunction "2B1_5") (pintype "passive"))
    )
    (net (code "124") (name "USER_LED3") (class "Default")
      (node (ref "U18") (pin "11") (pinfunction "3B1_11") (pintype "passive"))
    )
    (net (code "125") (name "USER_LED4") (class "Default")
      (node (ref "U18") (pin "14") (pinfunction "4B1_14") (pintype "passive"))
    )
    (net (code "126") (name "USER_SW1") (class "Default")
      (node (ref "U16") (pin "2") (pinfunction "1B1_2") (pintype "passive"))
    )
    (net (code "127") (name "USER_SW2") (class "Default")
      (node (ref "U16") (pin "5") (pinfunction "2B1_5") (pintype "passive"))
    )
    (net (code "128") (name "USER_SW3") (class "Default")
      (node (ref "U16") (pin "11") (pinfunction "3B1_11") (pintype "passive"))
    )
    (net (code "129") (name "USER_SW4") (class "Default")
      (node (ref "U16") (pin "14") (pinfunction "4B1_14") (pintype "passive"))
    )
    (net (code "130") (name "VCC_3V3") (class "Default")
      (node (ref "C265") (pin "1") (pinfunction "1_1") (pintype "passive"))
      (node (ref "C40") (pin "1") (pinfunction "1_1") (pintype "passive"))
      (node (ref "C41") (pin "1") (pinfunction "1_1") (pintype "passive"))
      (node (ref "C42") (pin "1") (pinfunction "1_1") (pintype "passive"))
      (node (ref "C43") (pin "1") (pinfunction "1_1") (pintype "passive"))
      (node (ref "U16") (pin "16") (pinfunction "VCC_16") (pintype "passive"))
      (node (ref "U17") (pin "16") (pinfunction "VCC_16") (pintype "passive"))
      (node (ref "U18") (pin "16") (pinfunction "VCC_16") (pintype "passive"))
      (node (ref "U19") (pin "16") (pinfunction "VIN_16") (pintype "input"))
      (node (ref "U58") (pin "16") (pinfunction "VCC_16") (pintype "passive"))
    )
    (net (code "131") (name "unconnected-(RN11-Pad1)") (class "Default")
      (node (ref "RN11") (pin "1") (pinfunction "1_1") (pintype "passive"))
    )
    (net (code "132") (name "unconnected-(RN11-Pad16)") (class "Default")
      (node (ref "RN11") (pin "16") (pinfunction "16_16") (pintype "passive"))
    )
    (net (code "133") (name "unconnected-(U19-2B2-Pad11)") (class "Default")
      (node (ref "U19") (pin "11") (pinfunction "2B2_11") (pintype "passive"))
    )
    (net (code "134") (name "unconnected-(U58-2B1-Pad5)") (class "Default")
      (node (ref "U58") (pin "5") (pinfunction "2B1_5") (pintype "passive"))
    )
    (net (code "135") (name "unconnected-(U58-2B2-Pad6)") (class "Default")
      (node (ref "U58") (pin "6") (pinfunction "2B2_6") (pintype "passive"))
    )
    (net (code "136") (name "unconnected-(U58-3B1-Pad11)") (class "Default")
      (node (ref "U58") (pin "11") (pinfunction "3B1_11") (pintype "passive"))
    )
    (net (code "137") (name "unconnected-(U58-3B2-Pad10)") (class "Default")
      (node (ref "U58") (pin "10") (pinfunction "3B2_10") (pintype "passive"))
    )
    (net (code "138") (name "unconnected-(U58-4B1-Pad14)") (class "Default")
      (node (ref "U58") (pin "14") (pinfunction "4B1_14") (pintype "passive"))
    )
    (net (code "139") (name "unconnected-(U58-4B2-Pad13)") (class "Default")
      (node (ref "U58") (pin "13") (pinfunction "4B2_13") (pintype "passive"))
    )
  )
)
